# Core.net
KiCad netlist of a schematic drawn in Altium Designer
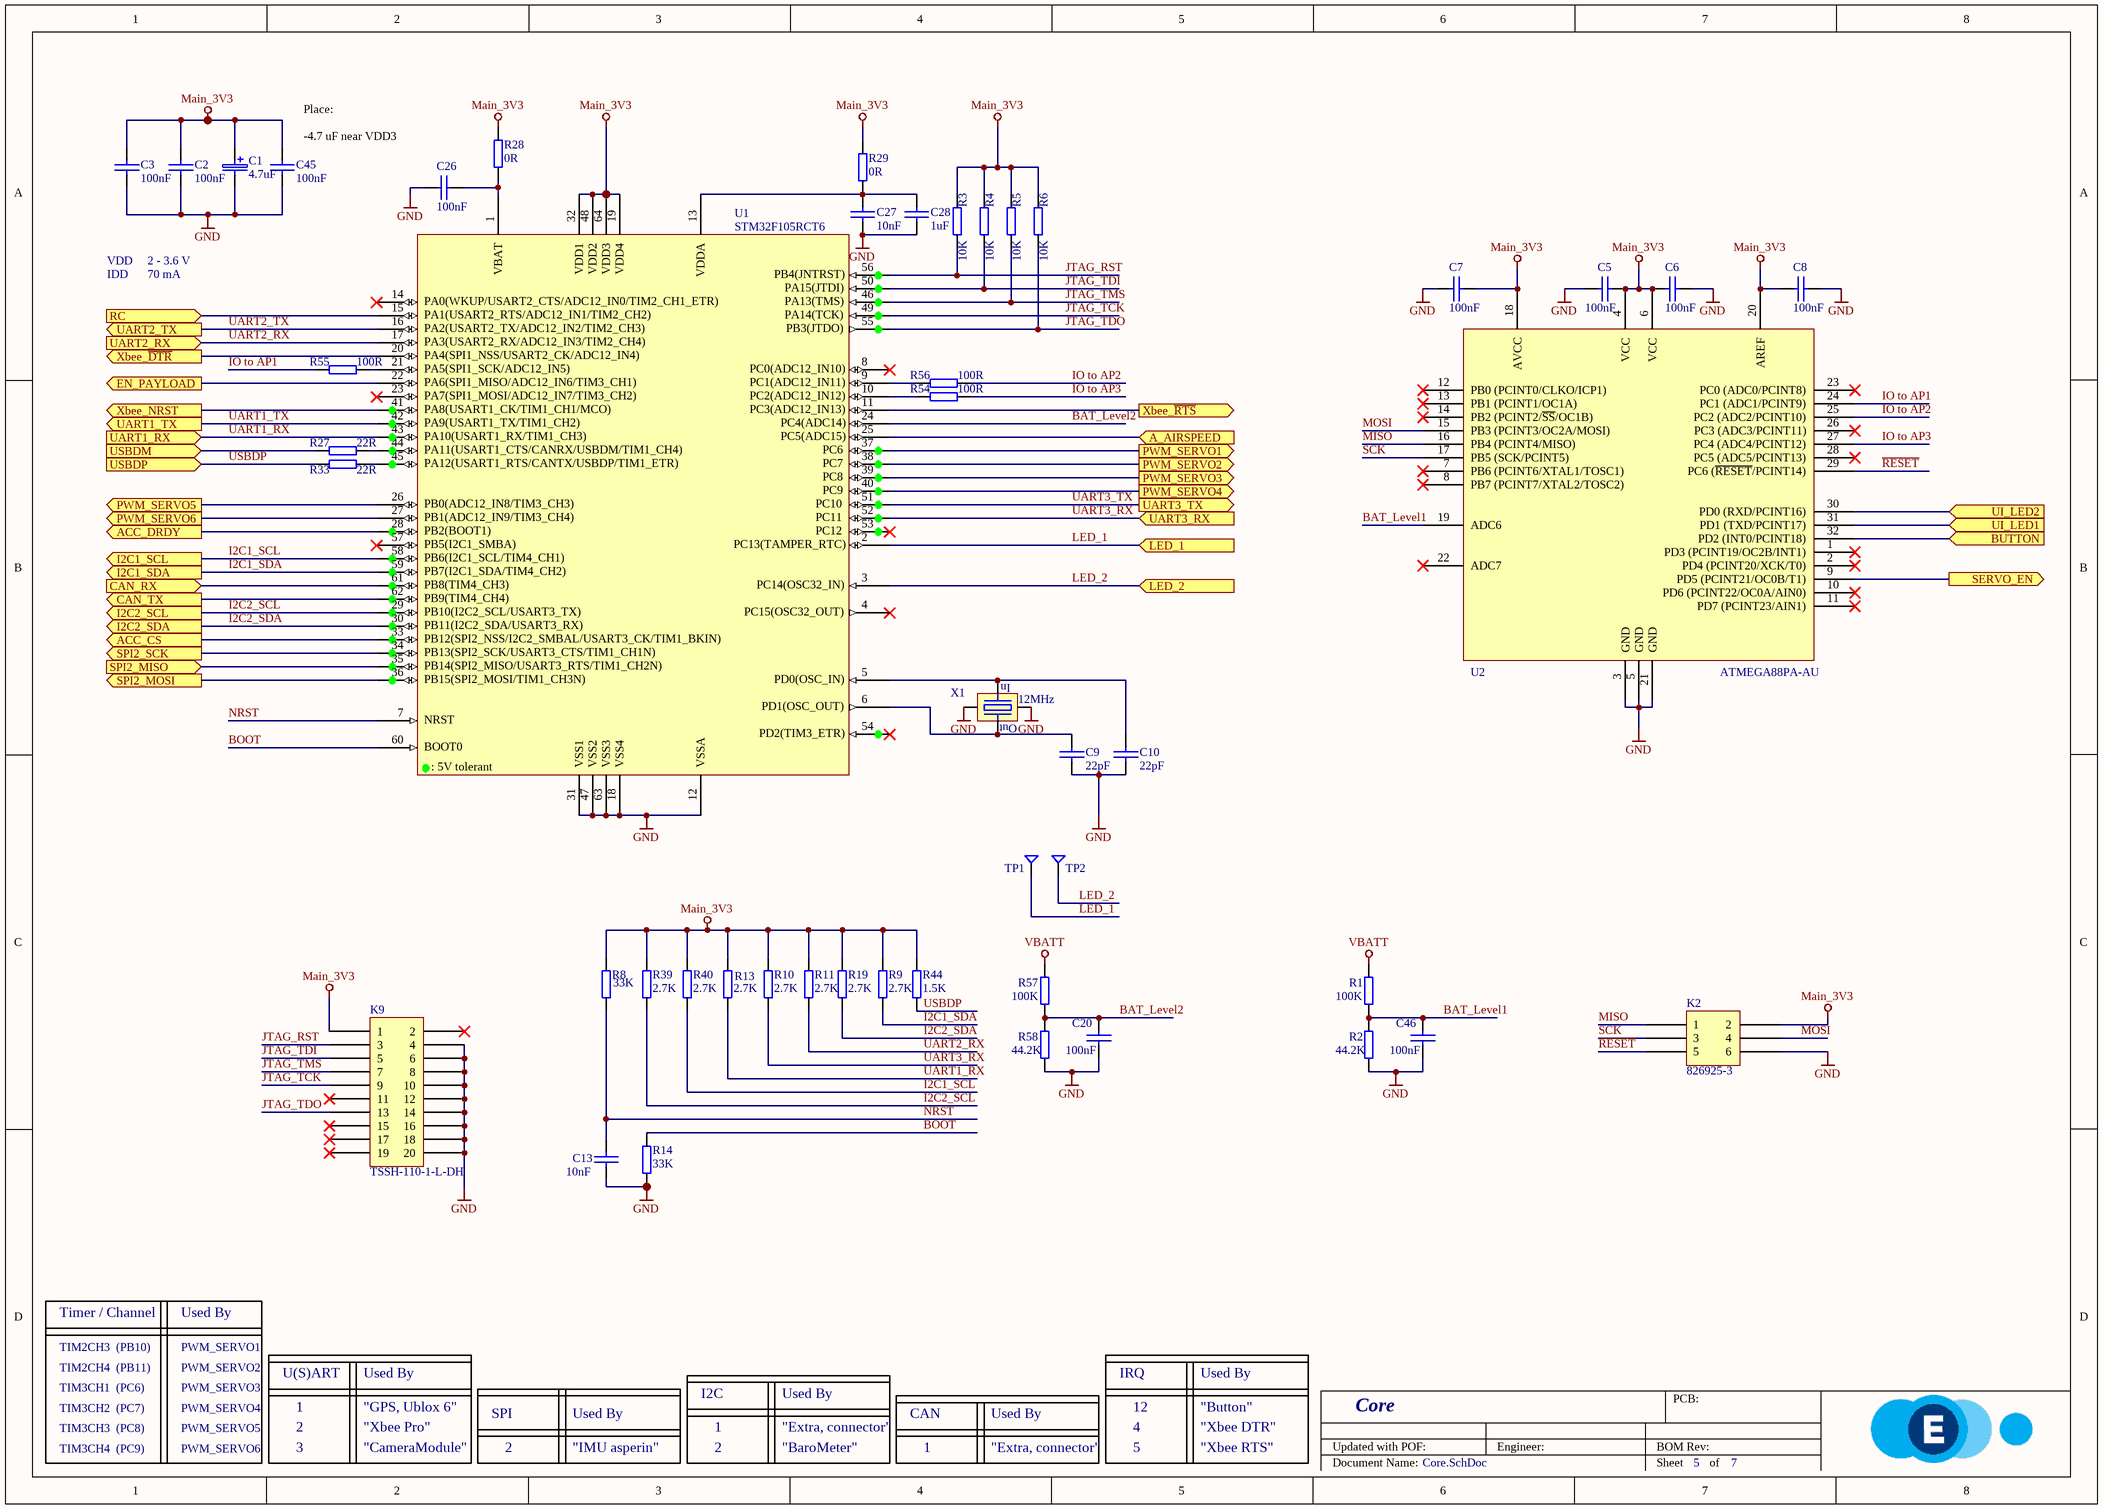
[diagram p0: Core.SchDoc]

(export (version "E")
  (design (tool "Eeschema 10.0.6"))
  (components
    (comp (ref "C1")
      (value "4.7uF")
      (footprint "C_TANT_A_CAL")
      (description "Capacitor, tantalum")
      (fields (field (name "MANUFACTURER") "AVX") (field (name "MAN. PART NO") "TAJA475K010R"))
      (libsource (lib "SE_db_helios") (part "C12"))
    )
    (comp (ref "C2")
      (value "100nF")
      (footprint "C0603_CAL")
      (description "Capacitor, ceramic")
      (fields (field (name "TOLERANCE") "10%") (field (name "Comment") "C11"))
      (libsource (lib "SE_db_helios") (part "C11"))
    )
    (comp (ref "C3")
      (value "100nF")
      (footprint "C0603_CAL")
      (description "Capacitor, ceramic")
      (fields (field (name "TOLERANCE") "10%") (field (name "Comment") "C11"))
      (libsource (lib "SE_db_helios") (part "C11"))
    )
    (comp (ref "C5")
      (value "100nF")
      (footprint "C0603_CAL")
      (description "Capacitor, ceramic")
      (fields (field (name "TOLERANCE") "10%") (field (name "Comment") "C11"))
      (libsource (lib "SE_db_helios") (part "C11"))
    )
    (comp (ref "C6")
      (value "100nF")
      (footprint "C0603_CAL")
      (description "Capacitor, ceramic")
      (fields (field (name "TOLERANCE") "10%") (field (name "Comment") "C11"))
      (libsource (lib "SE_db_helios") (part "C11"))
    )
    (comp (ref "C7")
      (value "100nF")
      (footprint "C0603_CAL")
      (description "Capacitor, ceramic")
      (fields (field (name "TOLERANCE") "10%") (field (name "Comment") "C11"))
      (libsource (lib "SE_db_helios") (part "C11"))
    )
    (comp (ref "C8")
      (value "100nF")
      (footprint "C0603_CAL")
      (description "Capacitor, ceramic")
      (fields (field (name "TOLERANCE") "10%") (field (name "Comment") "C11"))
      (libsource (lib "SE_db_helios") (part "C11"))
    )
    (comp (ref "C9")
      (value "22pF")
      (footprint "C0603_CAL")
      (description "Capacitor, ceramic")
      (fields (field (name "TOLERANCE") "5%") (field (name "Comment") "C11"))
      (libsource (lib "SE_db_helios") (part "C11"))
    )
    (comp (ref "C10")
      (value "22pF")
      (footprint "C0603_CAL")
      (description "Capacitor, ceramic")
      (fields (field (name "TOLERANCE") "5%") (field (name "Comment") "C11"))
      (libsource (lib "SE_db_helios") (part "C11"))
    )
    (comp (ref "C13")
      (value "10nF")
      (footprint "C0603_CAL")
      (description "Capacitor, ceramic")
      (fields (field (name "TOLERANCE") "10%") (field (name "Comment") "C11"))
      (libsource (lib "SE_db_helios") (part "C11"))
    )
    (comp (ref "C20")
      (value "100nF")
      (footprint "C0603_CAL")
      (description "Capacitor, ceramic")
      (fields (field (name "TOLERANCE") "10%") (field (name "Comment") "C11"))
      (libsource (lib "SE_db_helios") (part "C11"))
    )
    (comp (ref "C26")
      (value "100nF")
      (footprint "C0603_CAL")
      (description "Capacitor, ceramic")
      (fields (field (name "TOLERANCE") "10%") (field (name "Comment") "C11"))
      (libsource (lib "SE_db_helios") (part "C11"))
    )
    (comp (ref "C27")
      (value "10nF")
      (footprint "C0603_CAL")
      (description "Capacitor, ceramic")
      (fields (field (name "TOLERANCE") "10%") (field (name "Comment") "C11"))
      (libsource (lib "SE_db_helios") (part "C11"))
    )
    (comp (ref "C28")
      (value "1uF")
      (footprint "C0805_CAL")
      (description "Capacitor, ceramic")
      (fields (field (name "MANUFACTURER") "Kemet") (field (name "MAN. PART NO") "C0805C105K3RACTU"))
      (libsource (lib "SE_db_helios") (part "C11"))
    )
    (comp (ref "C45")
      (value "100nF")
      (footprint "C0603_CAL")
      (description "Capacitor, ceramic")
      (fields (field (name "TOLERANCE") "10%") (field (name "Comment") "C11"))
      (libsource (lib "SE_db_helios") (part "C11"))
    )
    (comp (ref "C46")
      (value "100nF")
      (footprint "C0603_CAL")
      (description "Capacitor, ceramic")
      (fields (field (name "TOLERANCE") "10%") (field (name "Comment") "C11"))
      (libsource (lib "SE_db_helios") (part "C11"))
    )
    (comp (ref "K2")
      (value "826925-3")
      (footprint "6pins, two row")
      (description "2x3 way, header, 2,54mm")
      (fields (field (name "MANUFACTURER") "TE Connectivity / AMP"))
      (libsource (lib "AutoPilot") (part "826925-3"))
    )
    (comp (ref "K9")
      (value "TSSH-110-1-L-DH")
      (footprint "TSSH-110-01-L-DH")
      (description "Header, 2,54mm, Shrouded, 2x10way")
      (fields (field (name "MANUFACTURER") "Samtec") (field (name "MAN. PART NO") "EJH-110-1-F-D-TH"))
      (libsource (lib "AutoPilot") (part "TSSH-110-1-L-DH"))
    )
    (comp (ref "R1")
      (value "100K")
      (footprint "R0603_CAL")
      (description "Resistor")
      (fields (field (name "TOLERANCE") "1%") (field (name "Comment") "R12"))
      (libsource (lib "SE_db_helios") (part "R12"))
    )
    (comp (ref "R2")
      (value "44.2K")
      (footprint "R0603_CAL")
      (description "Resistor")
      (fields (field (name "TOLERANCE") "1%") (field (name "Comment") "R12"))
      (libsource (lib "SE_db_helios") (part "R12"))
    )
    (comp (ref "R3")
      (value "10K")
      (footprint "R0603_CAL")
      (description "Resistor")
      (fields (field (name "TOLERANCE") "1%") (field (name "Comment") "R12"))
      (libsource (lib "SE_db_helios") (part "R12"))
    )
    (comp (ref "R4")
      (value "10K")
      (footprint "R0603_CAL")
      (description "Resistor")
      (fields (field (name "TOLERANCE") "1%") (field (name "Comment") "R12"))
      (libsource (lib "SE_db_helios") (part "R12"))
    )
    (comp (ref "R5")
      (value "10K")
      (footprint "R0603_CAL")
      (description "Resistor")
      (fields (field (name "TOLERANCE") "1%") (field (name "Comment") "R12"))
      (libsource (lib "SE_db_helios") (part "R12"))
    )
    (comp (ref "R6")
      (value "10K")
      (footprint "R0603_CAL")
      (description "Resistor")
      (fields (field (name "TOLERANCE") "1%") (field (name "Comment") "R12"))
      (libsource (lib "SE_db_helios") (part "R12"))
    )
    (comp (ref "R8")
      (value "33K")
      (footprint "R0603_CAL")
      (description "Resistor")
      (fields (field (name "TOLERANCE") "1%") (field (name "Comment") "R12"))
      (libsource (lib "SE_db_helios") (part "R12"))
    )
    (comp (ref "R9")
      (value "2.7K")
      (footprint "R0603_CAL")
      (description "Resistor")
      (fields (field (name "TOLERANCE") "1%") (field (name "Comment") "R12"))
      (libsource (lib "SE_db_helios") (part "R12"))
    )
    (comp (ref "R10")
      (value "2.7K")
      (footprint "R0603_CAL")
      (description "Resistor")
      (fields (field (name "TOLERANCE") "1%") (field (name "Comment") "R12"))
      (libsource (lib "SE_db_helios") (part "R12"))
    )
    (comp (ref "R11")
      (value "2.7K")
      (footprint "R0603_CAL")
      (description "Resistor")
      (fields (field (name "TOLERANCE") "1%") (field (name "Comment") "R12"))
      (libsource (lib "SE_db_helios") (part "R12"))
    )
    (comp (ref "R13")
      (value "2.7K")
      (footprint "R0603_CAL")
      (description "Resistor")
      (fields (field (name "TOLERANCE") "1%") (field (name "Comment") "R12"))
      (libsource (lib "SE_db_helios") (part "R12"))
    )
    (comp (ref "R14")
      (value "33K")
      (footprint "R0603_CAL")
      (description "Resistor")
      (fields (field (name "TOLERANCE") "1%") (field (name "Comment") "R12"))
      (libsource (lib "SE_db_helios") (part "R12"))
    )
    (comp (ref "R19")
      (value "2.7K")
      (footprint "R0603_CAL")
      (description "Resistor")
      (fields (field (name "TOLERANCE") "1%") (field (name "Comment") "R12"))
      (libsource (lib "SE_db_helios") (part "R12"))
    )
    (comp (ref "R27")
      (value "22R")
      (footprint "R0603_CAL")
      (description "Resistor")
      (fields (field (name "TOLERANCE") "1%") (field (name "Comment") "R12"))
      (libsource (lib "SE_db_helios") (part "R12"))
    )
    (comp (ref "R28")
      (value "0R")
      (footprint "R0603_CAL")
      (description "Resistor")
      (fields (field (name "TOLERANCE") "1%") (field (name "Comment") "R12"))
      (libsource (lib "SE_db_helios") (part "R12"))
    )
    (comp (ref "R29")
      (value "0R")
      (footprint "R0603_CAL")
      (description "Resistor")
      (fields (field (name "TOLERANCE") "1%") (field (name "Comment") "R12"))
      (libsource (lib "SE_db_helios") (part "R12"))
    )
    (comp (ref "R33")
      (value "22R")
      (footprint "R0603_CAL")
      (description "Resistor")
      (fields (field (name "TOLERANCE") "1%") (field (name "Comment") "R12"))
      (libsource (lib "SE_db_helios") (part "R12"))
    )
    (comp (ref "R39")
      (value "2.7K")
      (footprint "R0603_CAL")
      (description "Resistor")
      (fields (field (name "TOLERANCE") "1%") (field (name "Comment") "R12"))
      (libsource (lib "SE_db_helios") (part "R12"))
    )
    (comp (ref "R40")
      (value "2.7K")
      (footprint "R0603_CAL")
      (description "Resistor")
      (fields (field (name "TOLERANCE") "1%") (field (name "Comment") "R12"))
      (libsource (lib "SE_db_helios") (part "R12"))
    )
    (comp (ref "R44")
      (value "1.5K")
      (footprint "R0603_CAL")
      (description "Resistor")
      (fields (field (name "TOLERANCE") "1%") (field (name "Comment") "R12"))
      (libsource (lib "SE_db_helios") (part "R12"))
    )
    (comp (ref "R54")
      (value "100R")
      (footprint "R0603_CAL")
      (description "Resistor")
      (fields (field (name "TOLERANCE") "1%") (field (name "Comment") "R12"))
      (libsource (lib "SE_db_helios") (part "R12"))
    )
    (comp (ref "R55")
      (value "100R")
      (footprint "R0603_CAL")
      (description "Resistor")
      (fields (field (name "TOLERANCE") "1%") (field (name "Comment") "R12"))
      (libsource (lib "SE_db_helios") (part "R12"))
    )
    (comp (ref "R56")
      (value "100R")
      (footprint "R0603_CAL")
      (description "Resistor")
      (fields (field (name "TOLERANCE") "1%") (field (name "Comment") "R12"))
      (libsource (lib "SE_db_helios") (part "R12"))
    )
    (comp (ref "R57")
      (value "100K")
      (footprint "R0603_CAL")
      (description "Resistor")
      (fields (field (name "TOLERANCE") "1%") (field (name "Comment") "R12"))
      (libsource (lib "SE_db_helios") (part "R12"))
    )
    (comp (ref "R58")
      (value "44.2K")
      (footprint "R0603_CAL")
      (description "Resistor")
      (fields (field (name "TOLERANCE") "1%") (field (name "Comment") "R12"))
      (libsource (lib "SE_db_helios") (part "R12"))
    )
    (comp (ref "TP1")
      (value "PCB7")
      (footprint "TP_SMT_1.5MM")
      (description "Testpad")
      (libsource (lib "SE_db_helios") (part "PCB7"))
    )
    (comp (ref "TP2")
      (value "PCB7")
      (footprint "TP_SMT_1.5MM")
      (description "Testpad")
      (libsource (lib "SE_db_helios") (part "PCB7"))
    )
    (comp (ref "U1")
      (value "uC STM32F105RC")
      (footprint "LQFP64")
      (description "Microcontroller, ARM 32-bit, Mainstream")
      (fields (field (name "MANUFACTURER") "ST") (field (name "MAN. PART NO") "STM32F105RCT6"))
      (libsource (lib "AutoPilot") (part "uC STM32F105RC"))
    )
    (comp (ref "U2")
      (value "ATMEGA88")
      (footprint "TQFP32")
      (description "ATMEL - ATMEGA88PA-AU - MCU, 8BIT, AVR, 8K FLASH, 32 TQFP")
      (fields (field (name "MANUFACTURER") "ATMEL") (field (name "MAN. PART NO") "ATMEGA88PA-AU"))
      (libsource (lib "AutoPilot") (part "ATMEGA88"))
    )
    (comp (ref "X1")
      (value "Crystal")
      (footprint "ECS-120-20-33-CKM-TR")
      (description "CRYSTAL 12.000 MHZ 20PF SMD")
      (fields
        (field (name "MANUFACTURER") "ECS Inc")
        (field (name "MAN. PART NO") "ECS-120-20-33-CKM-TR")
        (field (name "FREQUENCY") "12MHz")
      )
      (libsource (lib "AutoPilot") (part "Crystal"))
    )
  )
  (nets
    (net (code "1") (name "/ACC_CS") (class "Default")
      (node (ref "U1") (pin "33") (pinfunction "33_33") (pintype "bidirectional"))
    )
    (net (code "2") (name "/ACC_DRDY") (class "Default")
      (node (ref "U1") (pin "28") (pinfunction "PB2(BOOT1)_28") (pintype "bidirectional"))
    )
    (net (code "3") (name "/A_AIRSPEED") (class "Default")
      (node (ref "U1") (pin "25") (pinfunction "PC5(ADC15)_25") (pintype "bidirectional"))
    )
    (net (code "4") (name "/BAT_Level1") (class "Default")
      (node (ref "C46") (pin "2") (pintype "passive"))
      (node (ref "R1") (pin "1") (pintype "passive"))
      (node (ref "R2") (pin "2") (pintype "passive"))
      (node (ref "U2") (pin "19") (pinfunction "ADC6_19") (pintype "passive"))
    )
    (net (code "5") (name "/BAT_Level2") (class "Default")
      (node (ref "C20") (pin "2") (pintype "passive"))
      (node (ref "R57") (pin "1") (pintype "passive"))
      (node (ref "R58") (pin "2") (pintype "passive"))
      (node (ref "U1") (pin "24") (pinfunction "PC4(ADC14)_24") (pintype "bidirectional"))
    )
    (net (code "6") (name "/BOOT") (class "Default")
      (node (ref "R14") (pin "2") (pintype "passive"))
      (node (ref "U1") (pin "60") (pinfunction "BOOT0_60") (pintype "input"))
    )
    (net (code "7") (name "/BUTTON") (class "Default")
      (node (ref "U2") (pin "32") (pinfunction "PD2_(INT0/PCINT18)_32") (pintype "passive"))
    )
    (net (code "8") (name "/CAN_RX") (class "Default")
      (node (ref "U1") (pin "61") (pinfunction "61_61") (pintype "bidirectional"))
    )
    (net (code "9") (name "/CAN_TX") (class "Default")
      (node (ref "U1") (pin "62") (pinfunction "62_62") (pintype "bidirectional"))
    )
    (net (code "10") (name "/EN_PAYLOAD") (class "Default")
      (node (ref "U1") (pin "22") (pinfunction "22_22") (pintype "bidirectional"))
    )
    (net (code "11") (name "/I2C1_SCL") (class "Default")
      (node (ref "R40") (pin "1") (pintype "passive"))
      (node (ref "U1") (pin "58") (pinfunction "PB6(I2C1_SCL/TIM4_CH1)_58") (pintype "bidirectional"))
    )
    (net (code "12") (name "/I2C1_SDA") (class "Default")
      (node (ref "R9") (pin "1") (pintype "passive"))
      (node (ref "U1") (pin "59") (pinfunction "59_59") (pintype "bidirectional"))
    )
    (net (code "13") (name "/I2C2_SCL") (class "Default")
      (node (ref "R39") (pin "1") (pintype "passive"))
      (node (ref "U1") (pin "29") (pinfunction "PB10(I2C2_SCL/USART3_TX)_29") (pintype "bidirectional"))
    )
    (net (code "14") (name "/I2C2_SDA") (class "Default")
      (node (ref "R19") (pin "1") (pintype "passive"))
      (node (ref "U1") (pin "30") (pinfunction "PB11(I2C2_SDA/USART3_RX)_30") (pintype "bidirectional"))
    )
    (net (code "15") (name "/IO to AP1") (class "Default")
      (node (ref "R55") (pin "2") (pintype "passive"))
      (node (ref "U2") (pin "24") (pinfunction "PC1_(ADC1/PCINT9)_24") (pintype "passive"))
    )
    (net (code "16") (name "/IO to AP2") (class "Default")
      (node (ref "R56") (pin "2") (pintype "passive"))
      (node (ref "U2") (pin "25") (pinfunction "PC2_(ADC2/PCINT10)_25") (pintype "passive"))
    )
    (net (code "17") (name "/IO to AP3") (class "Default")
      (node (ref "R54") (pin "1") (pintype "passive"))
      (node (ref "U2") (pin "27") (pinfunction "PC4_(ADC4/PCINT12)_27") (pintype "passive"))
    )
    (net (code "18") (name "/JTAG_RST") (class "Default")
      (node (ref "K9") (pin "3") (pinfunction "3_3") (pintype "passive"))
      (node (ref "R3") (pin "1") (pintype "passive"))
      (node (ref "U1") (pin "56") (pinfunction "56_56") (pintype "input"))
    )
    (net (code "19") (name "/JTAG_TCK") (class "Default")
      (node (ref "K9") (pin "9") (pinfunction "9_9") (pintype "passive"))
      (node (ref "U1") (pin "49") (pinfunction "PA14(TCK)_49") (pintype "input"))
    )
    (net (code "20") (name "/JTAG_TDI") (class "Default")
      (node (ref "K9") (pin "5") (pinfunction "5_5") (pintype "passive"))
      (node (ref "R4") (pin "1") (pintype "passive"))
      (node (ref "U1") (pin "50") (pinfunction "50_50") (pintype "input"))
    )
    (net (code "21") (name "/JTAG_TDO") (class "Default")
      (node (ref "K9") (pin "13") (pinfunction "13_13") (pintype "passive"))
      (node (ref "R6") (pin "1") (pintype "passive"))
      (node (ref "U1") (pin "55") (pinfunction "55_55") (pintype "output"))
    )
    (net (code "22") (name "/JTAG_TMS") (class "Default")
      (node (ref "K9") (pin "7") (pinfunction "7_7") (pintype "passive"))
      (node (ref "R5") (pin "1") (pintype "passive"))
      (node (ref "U1") (pin "46") (pinfunction "PA13(TMS)_46") (pintype "input"))
    )
    (net (code "23") (name "/LED_1") (class "Default")
      (node (ref "TP1") (pin "1") (pintype "passive"))
      (node (ref "U1") (pin "2") (pinfunction "PC13(TAMPER_RTC)_2") (pintype "bidirectional"))
    )
    (net (code "24") (name "/LED_2") (class "Default")
      (node (ref "TP2") (pin "1") (pintype "passive"))
      (node (ref "U1") (pin "3") (pinfunction "PC14(OSC32_IN)_3") (pintype "input"))
    )
    (net (code "25") (name "/MISO") (class "Default")
      (node (ref "K2") (pin "1") (pinfunction "1_1") (pintype "passive"))
      (node (ref "U2") (pin "16") (pinfunction "PB4_(PCINT4/MISO)_16") (pintype "passive"))
    )
    (net (code "26") (name "/MOSI") (class "Default")
      (node (ref "K2") (pin "4") (pinfunction "4_4") (pintype "passive"))
      (node (ref "U2") (pin "15") (pinfunction "PB3_(PCINT3/OC2A/MOSI)_15") (pintype "passive"))
    )
    (net (code "27") (name "/NRST") (class "Default")
      (node (ref "C13") (pin "2") (pintype "passive"))
      (node (ref "R8") (pin "1") (pintype "passive"))
      (node (ref "U1") (pin "7") (pinfunction "NRST_7") (pintype "input"))
    )
    (net (code "28") (name "/PWM_SERVO1") (class "Default")
      (node (ref "U1") (pin "37") (pinfunction "37_37") (pintype "bidirectional"))
    )
    (net (code "29") (name "/PWM_SERVO2") (class "Default")
      (node (ref "U1") (pin "38") (pinfunction "38_38") (pintype "bidirectional"))
    )
    (net (code "30") (name "/PWM_SERVO3") (class "Default")
      (node (ref "U1") (pin "39") (pinfunction "39_39") (pintype "bidirectional"))
    )
    (net (code "31") (name "/PWM_SERVO4") (class "Default")
      (node (ref "U1") (pin "40") (pinfunction "40_40") (pintype "bidirectional"))
    )
    (net (code "32") (name "/PWM_SERVO5") (class "Default")
      (node (ref "U1") (pin "26") (pinfunction "26_26") (pintype "bidirectional"))
    )
    (net (code "33") (name "/PWM_SERVO6") (class "Default")
      (node (ref "U1") (pin "27") (pinfunction "27_27") (pintype "bidirectional"))
    )
    (net (code "34") (name "/RC") (class "Default")
      (node (ref "U1") (pin "15") (pinfunction "15_15") (pintype "bidirectional"))
    )
    (net (code "35") (name "/SCK") (class "Default")
      (node (ref "K2") (pin "3") (pinfunction "3_3") (pintype "passive"))
      (node (ref "U2") (pin "17") (pinfunction "PB5_(SCK/PCINT5)_17") (pintype "passive"))
    )
    (net (code "36") (name "/SERVO_EN") (class "Default")
      (node (ref "U2") (pin "9") (pinfunction "PD5_(PCINT21/OC0B/T1)_9") (pintype "passive"))
    )
    (net (code "37") (name "/SPI2_MISO") (class "Default")
      (node (ref "U1") (pin "35") (pinfunction "PB14(SPI2_MISO/USART3_RTS/TIM1_CH2N)_35") (pintype "bidirectional"))
    )
    (net (code "38") (name "/SPI2_MOSI") (class "Default")
      (node (ref "U1") (pin "36") (pinfunction "35_36") (pintype "bidirectional"))
    )
    (net (code "39") (name "/SPI2_SCK") (class "Default")
      (node (ref "U1") (pin "34") (pinfunction "34_34") (pintype "bidirectional"))
    )
    (net (code "40") (name "/UART1_RX") (class "Default")
      (node (ref "R13") (pin "1") (pintype "passive"))
      (node (ref "U1") (pin "43") (pinfunction "PA10(USART1_RX/TIM1_CH3)_43") (pintype "bidirectional"))
    )
    (net (code "41") (name "/UART1_TX") (class "Default")
      (node (ref "U1") (pin "42") (pinfunction "PA9(USART1_TX/TIM1_CH2)_42") (pintype "bidirectional"))
    )
    (net (code "42") (name "/UART2_RX") (class "Default")
      (node (ref "R11") (pin "1") (pintype "passive"))
      (node (ref "U1") (pin "17") (pinfunction "17_17") (pintype "bidirectional"))
    )
    (net (code "43") (name "/UART2_TX") (class "Default")
      (node (ref "U1") (pin "16") (pinfunction "16_16") (pintype "bidirectional"))
    )
    (net (code "44") (name "/UART3_RX") (class "Default")
      (node (ref "R10") (pin "1") (pintype "passive"))
      (node (ref "U1") (pin "52") (pinfunction "52_52") (pintype "bidirectional"))
    )
    (net (code "45") (name "/UART3_TX") (class "Default")
      (node (ref "U1") (pin "51") (pinfunction "51_51") (pintype "bidirectional"))
    )
    (net (code "46") (name "/UI_LED1") (class "Default")
      (node (ref "U2") (pin "31") (pinfunction "PD1_(TXD/PCINT17)_31") (pintype "passive"))
    )
    (net (code "47") (name "/UI_LED2") (class "Default")
      (node (ref "U2") (pin "30") (pinfunction "PD0_(RXD/PCINT16)_30") (pintype "passive"))
    )
    (net (code "48") (name "/USBDM") (class "Default") (node (ref "R27") (pin "1") (pintype "passive")))
    (net (code "49") (name "/USBDP") (class "Default")
      (node (ref "R33") (pin "1") (pintype "passive"))
      (node (ref "R44") (pin "1") (pintype "passive"))
    )
    (net (code "50") (name "/Xbee_NRST") (class "Default")
      (node (ref "U1") (pin "41") (pinfunction "PA8(USART1_CK/TIM1_CH1/MCO)_41") (pintype "bidirectional"))
    )
    (net (code "51") (name "/Xbee_~{DTR}") (class "Default")
      (node (ref "U1") (pin "20") (pinfunction "20_20") (pintype "bidirectional"))
    )
    (net (code "52") (name "/Xbee_~{RTS}") (class "Default")
      (node (ref "U1") (pin "11") (pinfunction "11_11") (pintype "bidirectional"))
    )
    (net (code "53") (name "/~{RESET}") (class "Default")
      (node (ref "K2") (pin "5") (pinfunction "5_5") (pintype "passive"))
      (node (ref "U2") (pin "29") (pinfunction "PC6_(~{RESET}/PCINT14)_29") (pintype "passive"))
    )
    (net (code "54") (name "GND") (class "Default")
      (node (ref "C1") (pin "2") (pintype "passive"))
      (node (ref "C10") (pin "1") (pintype "passive"))
      (node (ref "C13") (pin "1") (pintype "passive"))
      (node (ref "C2") (pin "1") (pintype "passive"))
      (node (ref "C20") (pin "1") (pintype "passive"))
      (node (ref "C26") (pin "1") (pintype "passive"))
      (node (ref "C27") (pin "1") (pintype "passive"))
      (node (ref "C28") (pin "1") (pintype "passive"))
      (node (ref "C3") (pin "1") (pintype "passive"))
      (node (ref "C45") (pin "1") (pintype "passive"))
      (node (ref "C46") (pin "1") (pintype "passive"))
      (node (ref "C5") (pin "1") (pintype "passive"))
      (node (ref "C6") (pin "2") (pintype "passive"))
      (node (ref "C7") (pin "1") (pintype "passive"))
      (node (ref "C8") (pin "2") (pintype "passive"))
      (node (ref "C9") (pin "1") (pintype "passive"))
      (node (ref "K2") (pin "6") (pinfunction "6_6") (pintype "passive"))
      (node (ref "K9") (pin "10") (pinfunction "10_10") (pintype "passive"))
      (node (ref "K9") (pin "12") (pinfunction "12_12") (pintype "passive"))
      (node (ref "K9") (pin "14") (pinfunction "14_14") (pintype "passive"))
      (node (ref "K9") (pin "16") (pinfunction "16_16") (pintype "passive"))
      (node (ref "K9") (pin "18") (pinfunction "18_18") (pintype "passive"))
      (node (ref "K9") (pin "20") (pinfunction "20_20") (pintype "passive"))
      (node (ref "K9") (pin "4") (pinfunction "4_4") (pintype "passive"))
      (node (ref "K9") (pin "6") (pinfunction "6_6") (pintype "passive"))
      (node (ref "K9") (pin "8") (pinfunction "8_8") (pintype "passive"))
      (node (ref "R14") (pin "1") (pintype "passive"))
      (node (ref "R2") (pin "1") (pintype "passive"))
      (node (ref "R58") (pin "1") (pintype "passive"))
      (node (ref "U1") (pin "12") (pinfunction "VSSA_12") (pintype "power_in"))
      (node (ref "U1") (pin "18") (pinfunction "VSS4_18") (pintype "power_in"))
      (node (ref "U1") (pin "31") (pinfunction "VSS1_31") (pintype "power_in"))
      (node (ref "U1") (pin "47") (pinfunction "VSS2_47") (pintype "power_in"))
      (node (ref "U1") (pin "63") (pinfunction "VSS3_63") (pintype "power_in"))
      (node (ref "U2") (pin "21") (pinfunction "GND_21") (pintype "passive"))
      (node (ref "U2") (pin "3") (pinfunction "GND_3") (pintype "passive"))
      (node (ref "U2") (pin "5") (pinfunction "GND_5") (pintype "passive"))
      (node (ref "X1") (pin "2") (pinfunction "GND_2") (pintype "passive"))
      (node (ref "X1") (pin "4") (pinfunction "GND_4") (pintype "passive"))
    )
    (net (code "55") (name "Main_3V3") (class "Default")
      (node (ref "C1") (pin "1") (pintype "passive"))
      (node (ref "C2") (pin "2") (pintype "passive"))
      (node (ref "C3") (pin "2") (pintype "passive"))
      (node (ref "C45") (pin "2") (pintype "passive"))
      (node (ref "C5") (pin "2") (pintype "passive"))
      (node (ref "C6") (pin "1") (pintype "passive"))
      (node (ref "C7") (pin "2") (pintype "passive"))
      (node (ref "C8") (pin "1") (pintype "passive"))
      (node (ref "K2") (pin "2") (pinfunction "2_2") (pintype "passive"))
      (node (ref "K9") (pin "1") (pinfunction "1_1") (pintype "passive"))
      (node (ref "R10") (pin "2") (pintype "passive"))
      (node (ref "R11") (pin "2") (pintype "passive"))
      (node (ref "R13") (pin "2") (pintype "passive"))
      (node (ref "R19") (pin "2") (pintype "passive"))
      (node (ref "R28") (pin "2") (pintype "passive"))
      (node (ref "R29") (pin "2") (pintype "passive"))
      (node (ref "R3") (pin "2") (pintype "passive"))
      (node (ref "R39") (pin "2") (pintype "passive"))
      (node (ref "R4") (pin "2") (pintype "passive"))
      (node (ref "R40") (pin "2") (pintype "passive"))
      (node (ref "R44") (pin "2") (pintype "passive"))
      (node (ref "R5") (pin "2") (pintype "passive"))
      (node (ref "R6") (pin "2") (pintype "passive"))
      (node (ref "R8") (pin "2") (pintype "passive"))
      (node (ref "R9") (pin "2") (pintype "passive"))
      (node (ref "U1") (pin "19") (pinfunction "VDD4_19") (pintype "power_in"))
      (node (ref "U1") (pin "32") (pinfunction "VDD1_32") (pintype "power_in"))
      (node (ref "U1") (pin "48") (pinfunction "VDD2_48") (pintype "power_in"))
      (node (ref "U1") (pin "64") (pinfunction "VDD3_64") (pintype "power_in"))
      (node (ref "U2") (pin "18") (pinfunction "AVCC_18") (pintype "passive"))
      (node (ref "U2") (pin "20") (pinfunction "AREF_20") (pintype "passive"))
      (node (ref "U2") (pin "4") (pinfunction "VCC_4") (pintype "passive"))
      (node (ref "U2") (pin "6") (pinfunction "VCC_6") (pintype "passive"))
    )
    (net (code "56") (name "Net-(R54-Pad2)") (class "Default")
      (node (ref "R54") (pin "2") (pintype "passive"))
      (node (ref "U1") (pin "10") (pinfunction "10_10") (pintype "bidirectional"))
    )
    (net (code "57") (name "Net-(R55-Pad1)") (class "Default")
      (node (ref "R55") (pin "1") (pintype "passive"))
      (node (ref "U1") (pin "21") (pinfunction "21_21") (pintype "bidirectional"))
    )
    (net (code "58") (name "Net-(R56-Pad1)") (class "Default")
      (node (ref "R56") (pin "1") (pintype "passive"))
      (node (ref "U1") (pin "9") (pinfunction "9_9") (pintype "bidirectional"))
    )
    (net (code "59") (name "Net-(U1-PA11(USART1_CTS{slash}CANRX{slash}USBDM{slash}TIM1_CH4))") (class "Default")
      (node (ref "R27") (pin "2") (pintype "passive"))
      (node (ref "U1") (pin "44") (pinfunction "PA11(USART1_CTS/CANRX/USBDM/TIM1_CH4)_44") (pintype "bidirectional"))
    )
    (net (code "60") (name "Net-(U1-PA12(USART1_RTS{slash}CANTX{slash}USBDP{slash}TIM1_ETR))") (class "Default")
      (node (ref "R33") (pin "2") (pintype "passive"))
      (node (ref "U1") (pin "45") (pinfunction "PA12(USART1_RTS/CANTX/USBDP/TIM1_ETR)_45") (pintype "bidirectional"))
    )
    (net (code "61") (name "Net-(U1-VBAT)") (class "Default")
      (node (ref "C26") (pin "2") (pintype "passive"))
      (node (ref "R28") (pin "1") (pintype "passive"))
      (node (ref "U1") (pin "1") (pinfunction "VBAT_1") (pintype "power_in"))
    )
    (net (code "62") (name "Net-(U1-VDDA)") (class "Default")
      (node (ref "C27") (pin "2") (pintype "passive"))
      (node (ref "C28") (pin "2") (pintype "passive"))
      (node (ref "R29") (pin "1") (pintype "passive"))
      (node (ref "U1") (pin "13") (pinfunction "VDDA_13") (pintype "power_in"))
    )
    (net (code "63") (name "Net-(X1-In)") (class "Default")
      (node (ref "C10") (pin "2") (pintype "passive"))
      (node (ref "U1") (pin "5") (pinfunction "5_5") (pintype "input"))
      (node (ref "X1") (pin "1") (pinfunction "In_1") (pintype "passive"))
    )
    (net (code "64") (name "Net-(X1-Out)") (class "Default")
      (node (ref "C9") (pin "2") (pintype "passive"))
      (node (ref "U1") (pin "6") (pinfunction "6_6") (pintype "output"))
      (node (ref "X1") (pin "3") (pinfunction "Out_3") (pintype "passive"))
    )
    (net (code "65") (name "VBATT") (class "Default")
      (node (ref "R1") (pin "2") (pintype "passive"))
      (node (ref "R57") (pin "2") (pintype "passive"))
    )
    (net (code "66") (name "unconnected-(K9-Pad2)") (class "Default")
      (node (ref "K9") (pin "2") (pinfunction "2_2") (pintype "passive+no_connect"))
    )
    (net (code "67") (name "unconnected-(K9-Pad11)") (class "Default")
      (node (ref "K9") (pin "11") (pinfunction "11_11") (pintype "passive+no_connect"))
    )
    (net (code "68") (name "unconnected-(K9-Pad15)") (class "Default")
      (node (ref "K9") (pin "15") (pinfunction "15_15") (pintype "passive+no_connect"))
    )
    (net (code "69") (name "unconnected-(K9-Pad17)") (class "Default")
      (node (ref "K9") (pin "17") (pinfunction "17_17") (pintype "passive+no_connect"))
    )
    (net (code "70") (name "unconnected-(K9-Pad19)") (class "Default")
      (node (ref "K9") (pin "19") (pinfunction "19_19") (pintype "passive+no_connect"))
    )
    (net (code "71") (name "unconnected-(U1-PC15(OSC32_OUT)-Pad4)") (class "Default")
      (node (ref "U1") (pin "4") (pinfunction "PC15(OSC32_OUT)_4") (pintype "output+no_connect"))
    )
    (net (code "72") (name "unconnected-(U1-Pad8)") (class "Default")
      (node (ref "U1") (pin "8") (pinfunction "8_8") (pintype "bidirectional+no_connect"))
    )
    (net (code "73") (name "unconnected-(U1-Pad14)") (class "Default")
      (node (ref "U1") (pin "14") (pinfunction "14_14") (pintype "bidirectional+no_connect"))
    )
    (net (code "74") (name "unconnected-(U1-Pad23)") (class "Default")
      (node (ref "U1") (pin "23") (pinfunction "23_23") (pintype "bidirectional+no_connect"))
    )
    (net (code "75") (name "unconnected-(U1-Pad53)") (class "Default")
      (node (ref "U1") (pin "53") (pinfunction "53_53") (pintype "bidirectional+no_connect"))
    )
    (net (code "76") (name "unconnected-(U1-Pad54)") (class "Default")
      (node (ref "U1") (pin "54") (pinfunction "54_54") (pintype "input+no_connect"))
    )
    (net (code "77") (name "unconnected-(U1-Pad57)") (class "Default")
      (node (ref "U1") (pin "57") (pinfunction "57_57") (pintype "bidirectional+no_connect"))
    )
    (net (code "78") (name "unconnected-(U2-ADC7-Pad22)") (class "Default")
      (node (ref "U2") (pin "22") (pinfunction "ADC7_22") (pintype "passive+no_connect"))
    )
    (net (code "79") (name "unconnected-(U2-PB0_(PCINT0{slash}CLKO{slash}ICP1)-Pad12)") (class "Default")
      (node (ref "U2") (pin "12") (pinfunction "PB0_(PCINT0/CLKO/ICP1)_12") (pintype "passive+no_connect"))
    )
    (net (code "80") (name "unconnected-(U2-PB1_(PCINT1{slash}OC1A)-Pad13)") (class "Default")
      (node (ref "U2") (pin "13") (pinfunction "PB1_(PCINT1/OC1A)_13") (pintype "passive+no_connect"))
    )
    (net (code "81") (name "unconnected-(U2-PB2_(PCINT2{slash}~{SS}{slash}OC1B)-Pad14)") (class "Default")
      (node (ref "U2") (pin "14") (pinfunction "PB2_(PCINT2/~{SS}/OC1B)_14") (pintype "passive+no_connect"))
    )
    (net (code "82") (name "unconnected-(U2-PB6_(PCINT6{slash}XTAL1{slash}TOSC1)-Pad7)") (class "Default")
      (node (ref "U2") (pin "7") (pinfunction "PB6_(PCINT6/XTAL1/TOSC1)_7") (pintype "passive+no_connect"))
    )
    (net (code "83") (name "unconnected-(U2-PB7_(PCINT7{slash}XTAL2{slash}TOSC2)-Pad8)") (class "Default")
      (node (ref "U2") (pin "8") (pinfunction "PB7_(PCINT7/XTAL2/TOSC2)_8") (pintype "passive+no_connect"))
    )
    (net (code "84") (name "unconnected-(U2-PC0_(ADC0{slash}PCINT8)-Pad23)") (class "Default")
      (node (ref "U2") (pin "23") (pinfunction "PC0_(ADC0/PCINT8)_23") (pintype "passive+no_connect"))
    )
    (net (code "85") (name "unconnected-(U2-PC3_(ADC3{slash}PCINT11)-Pad26)") (class "Default")
      (node (ref "U2") (pin "26") (pinfunction "PC3_(ADC3/PCINT11)_26") (pintype "passive+no_connect"))
    )
    (net (code "86") (name "unconnected-(U2-PC5_(ADC5{slash}PCINT13)-Pad28)") (class "Default")
      (node (ref "U2") (pin "28") (pinfunction "PC5_(ADC5/PCINT13)_28") (pintype "passive+no_connect"))
    )
    (net (code "87") (name "unconnected-(U2-PD3_(PCINT19{slash}OC2B{slash}INT1)-Pad1)") (class "Default")
      (node (ref "U2") (pin "1") (pinfunction "PD3_(PCINT19/OC2B/INT1)_1") (pintype "passive+no_connect"))
    )
    (net (code "88") (name "unconnected-(U2-PD4_(PCINT20{slash}XCK{slash}T0)-Pad2)") (class "Default")
      (node (ref "U2") (pin "2") (pinfunction "PD4_(PCINT20/XCK/T0)_2") (pintype "passive+no_connect"))
    )
    (net (code "89") (name "unconnected-(U2-PD6_(PCINT22{slash}OC0A{slash}AIN0)-Pad10)") (class "Default")
      (node (ref "U2") (pin "10") (pinfunction "PD6_(PCINT22/OC0A/AIN0)_10") (pintype "passive+no_connect"))
    )
    (net (code "90") (name "unconnected-(U2-PD7_(PCINT23{slash}AIN1)-Pad11)") (class "Default")
      (node (ref "U2") (pin "11") (pinfunction "PD7_(PCINT23/AIN1)_11") (pintype "passive+no_connect"))
    )
  )
)
